# 04_-_BUTTON.net
KiCad netlist of a schematic drawn in Altium Designer
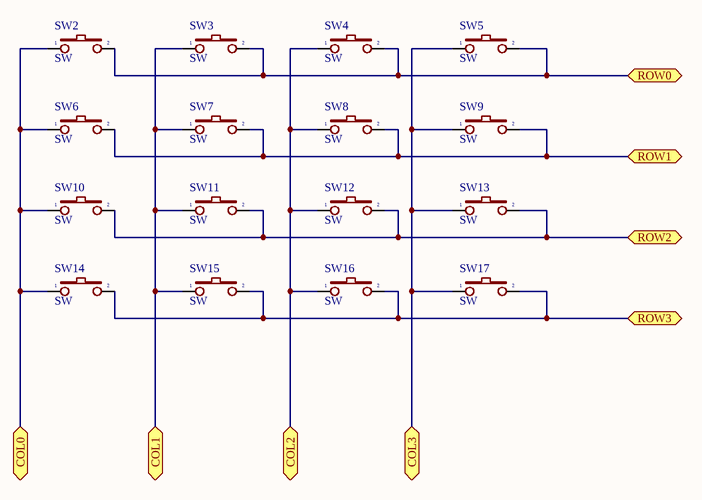
[diagram p0: [04] - BUTTON.SchDoc]

(export (version "E")
  (design (tool "Eeschema 10.0.6"))
  (components
    (comp (ref "SW2")
      (value "SW")
      (footprint "SW2")
      (description "Switch button 2 pin")
      (libsource (lib "My Library") (part "SW2"))
    )
    (comp (ref "SW3")
      (value "SW")
      (footprint "SW2")
      (description "Switch button 2 pin")
      (libsource (lib "My Library") (part "SW2"))
    )
    (comp (ref "SW4")
      (value "SW")
      (footprint "SW2")
      (description "Switch button 2 pin")
      (libsource (lib "My Library") (part "SW2"))
    )
    (comp (ref "SW5")
      (value "SW")
      (footprint "SW2")
      (description "Switch button 2 pin")
      (libsource (lib "My Library") (part "SW2"))
    )
    (comp (ref "SW6")
      (value "SW")
      (footprint "SW2")
      (description "Switch button 2 pin")
      (libsource (lib "My Library") (part "SW2"))
    )
    (comp (ref "SW7")
      (value "SW")
      (footprint "SW2")
      (description "Switch button 2 pin")
      (libsource (lib "My Library") (part "SW2"))
    )
    (comp (ref "SW8")
      (value "SW")
      (footprint "SW2")
      (description "Switch button 2 pin")
      (libsource (lib "My Library") (part "SW2"))
    )
    (comp (ref "SW9")
      (value "SW")
      (footprint "SW2")
      (description "Switch button 2 pin")
      (libsource (lib "My Library") (part "SW2"))
    )
    (comp (ref "SW10")
      (value "SW")
      (footprint "SW2")
      (description "Switch button 2 pin")
      (libsource (lib "My Library") (part "SW2"))
    )
    (comp (ref "SW11")
      (value "SW")
      (footprint "SW2")
      (description "Switch button 2 pin")
      (libsource (lib "My Library") (part "SW2"))
    )
    (comp (ref "SW12")
      (value "SW")
      (footprint "SW2")
      (description "Switch button 2 pin")
      (libsource (lib "My Library") (part "SW2"))
    )
    (comp (ref "SW13")
      (value "SW")
      (footprint "SW2")
      (description "Switch button 2 pin")
      (libsource (lib "My Library") (part "SW2"))
    )
    (comp (ref "SW14")
      (value "SW")
      (footprint "SW2")
      (description "Switch button 2 pin")
      (libsource (lib "My Library") (part "SW2"))
    )
    (comp (ref "SW15")
      (value "SW")
      (footprint "SW2")
      (description "Switch button 2 pin")
      (libsource (lib "My Library") (part "SW2"))
    )
    (comp (ref "SW16")
      (value "SW")
      (footprint "SW2")
      (description "Switch button 2 pin")
      (libsource (lib "My Library") (part "SW2"))
    )
    (comp (ref "SW17")
      (value "SW")
      (footprint "SW2")
      (description "Switch button 2 pin")
      (libsource (lib "My Library") (part "SW2"))
    )
  )
  (nets
    (net (code "1") (name "/COL0") (class "Default")
      (node (ref "SW10") (pin "1") (pinfunction "1_1") (pintype "passive"))
      (node (ref "SW14") (pin "1") (pinfunction "1_1") (pintype "passive"))
      (node (ref "SW2") (pin "1") (pinfunction "1_1") (pintype "passive"))
      (node (ref "SW6") (pin "1") (pinfunction "1_1") (pintype "passive"))
    )
    (net (code "2") (name "/COL1") (class "Default")
      (node (ref "SW11") (pin "1") (pinfunction "1_1") (pintype "passive"))
      (node (ref "SW15") (pin "1") (pinfunction "1_1") (pintype "passive"))
      (node (ref "SW3") (pin "1") (pinfunction "1_1") (pintype "passive"))
      (node (ref "SW7") (pin "1") (pinfunction "1_1") (pintype "passive"))
    )
    (net (code "3") (name "/COL2") (class "Default")
      (node (ref "SW12") (pin "1") (pinfunction "1_1") (pintype "passive"))
      (node (ref "SW16") (pin "1") (pinfunction "1_1") (pintype "passive"))
      (node (ref "SW4") (pin "1") (pinfunction "1_1") (pintype "passive"))
      (node (ref "SW8") (pin "1") (pinfunction "1_1") (pintype "passive"))
    )
    (net (code "4") (name "/COL3") (class "Default")
      (node (ref "SW13") (pin "1") (pinfunction "1_1") (pintype "passive"))
      (node (ref "SW17") (pin "1") (pinfunction "1_1") (pintype "passive"))
      (node (ref "SW5") (pin "1") (pinfunction "1_1") (pintype "passive"))
      (node (ref "SW9") (pin "1") (pinfunction "1_1") (pintype "passive"))
    )
    (net (code "5") (name "/ROW0") (class "Default")
      (node (ref "SW2") (pin "2") (pinfunction "2_2") (pintype "passive"))
      (node (ref "SW3") (pin "2") (pinfunction "2_2") (pintype "passive"))
      (node (ref "SW4") (pin "2") (pinfunction "2_2") (pintype "passive"))
      (node (ref "SW5") (pin "2") (pinfunction "2_2") (pintype "passive"))
    )
    (net (code "6") (name "/ROW1") (class "Default")
      (node (ref "SW6") (pin "2") (pinfunction "2_2") (pintype "passive"))
      (node (ref "SW7") (pin "2") (pinfunction "2_2") (pintype "passive"))
      (node (ref "SW8") (pin "2") (pinfunction "2_2") (pintype "passive"))
      (node (ref "SW9") (pin "2") (pinfunction "2_2") (pintype "passive"))
    )
    (net (code "7") (name "/ROW2") (class "Default")
      (node (ref "SW10") (pin "2") (pinfunction "2_2") (pintype "passive"))
      (node (ref "SW11") (pin "2") (pinfunction "2_2") (pintype "passive"))
      (node (ref "SW12") (pin "2") (pinfunction "2_2") (pintype "passive"))
      (node (ref "SW13") (pin "2") (pinfunction "2_2") (pintype "passive"))
    )
    (net (code "8") (name "/ROW3") (class "Default")
      (node (ref "SW14") (pin "2") (pinfunction "2_2") (pintype "passive"))
      (node (ref "SW15") (pin "2") (pinfunction "2_2") (pintype "passive"))
      (node (ref "SW16") (pin "2") (pinfunction "2_2") (pintype "passive"))
      (node (ref "SW17") (pin "2") (pinfunction "2_2") (pintype "passive"))
    )
  )
)
